# TrashFullnessSensor1_0_0.net
KiCad netlist of a schematic drawn in Altium Designer
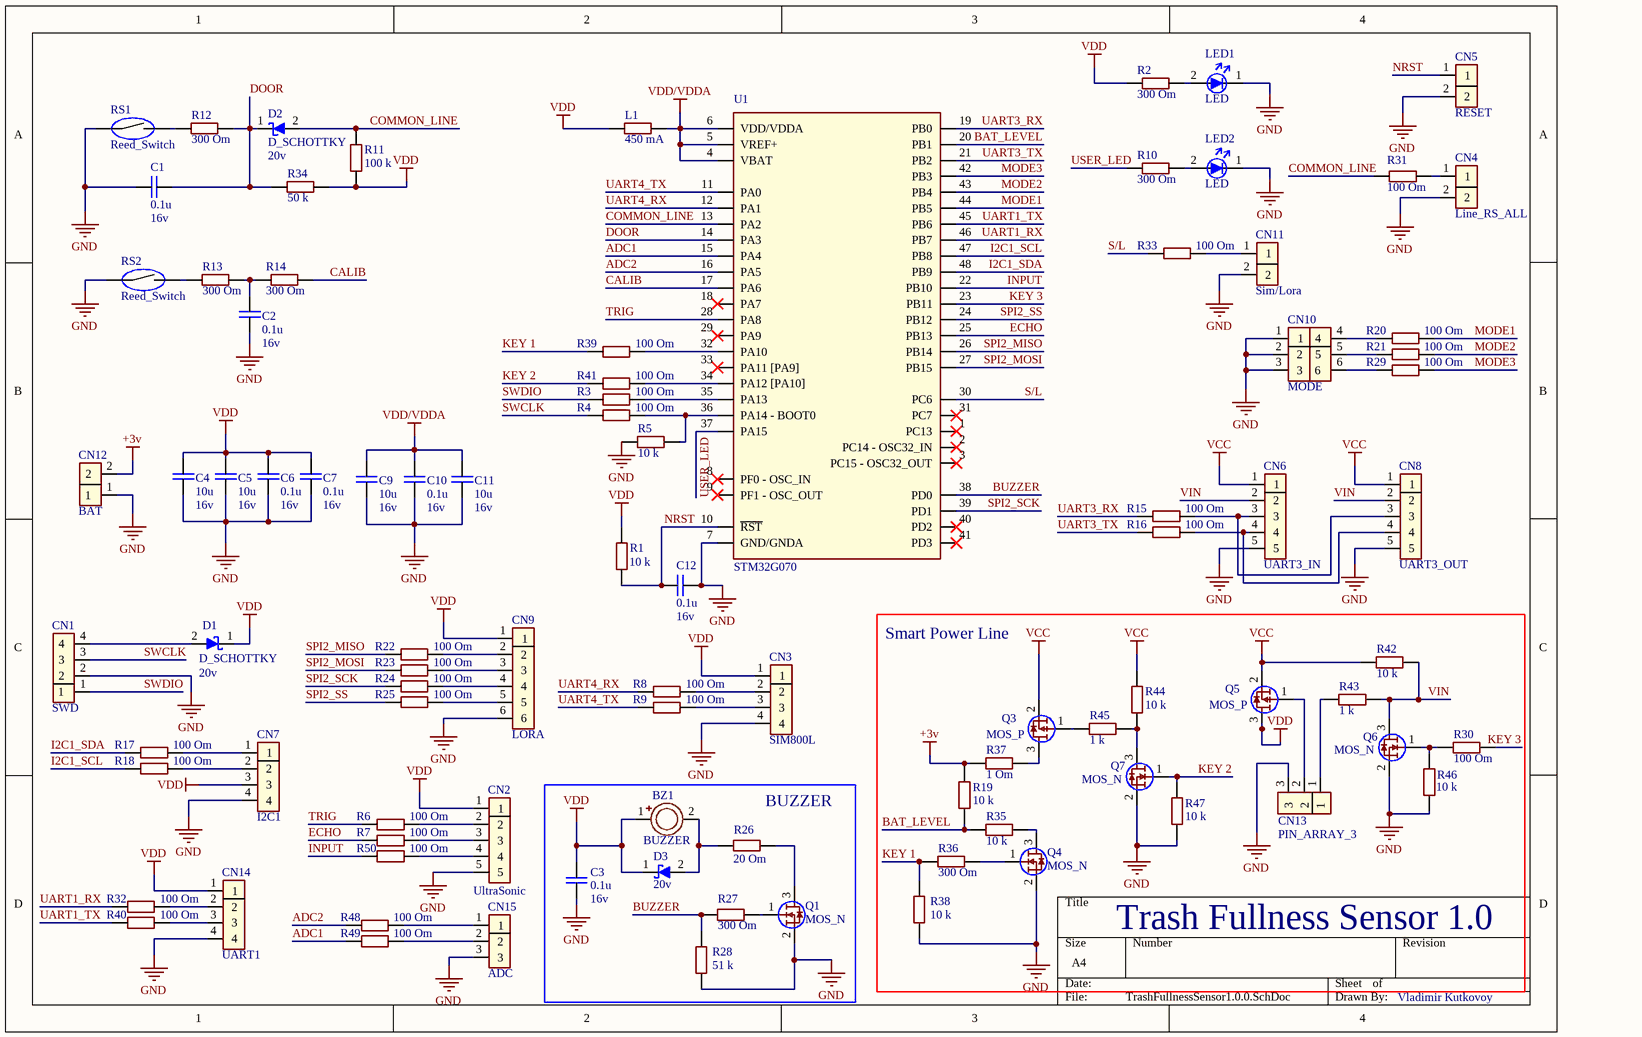
[diagram p0: TrashFullnessSensor1.0.0.SchDoc]

(export (version "E")
  (design (tool "Eeschema 10.0.6"))
  (components
    (comp (ref "BZ1") (value "BUZZER") (footprint "VK_Lib:BUZZER") (libsource (lib "Sound") (part "BUZZER")))
    (comp (ref "C1")
      (value "Capacitor")
      (footprint "VK_Lib:CAPC06003")
      (fields (field (name "СAPACITY") "0.1u") (field (name "VOLTAGE") "16v"))
      (libsource (lib "VK_Lib") (part "Capacitor"))
    )
    (comp (ref "C2")
      (value "Capacitor")
      (footprint "VK_Lib:CAP_0603")
      (fields (field (name "СAPACITY") "0.1u") (field (name "VOLTAGE") "16v"))
      (libsource (lib "PassiveComponents") (part "Capacitor"))
    )
    (comp (ref "C3")
      (value "Capacitor")
      (footprint "VK_Lib:CAP_0603")
      (fields (field (name "СAPACITY") "0.1u") (field (name "VOLTAGE") "16v"))
      (libsource (lib "PassiveComponents") (part "Capacitor"))
    )
    (comp (ref "C4")
      (value "~")
      (footprint "CAPC06003")
      (fields (field (name "СAPACITY") "10u") (field (name "VOLTAGE") "16v"))
      (libsource (lib "PassiveComponents") (part "Capacitor"))
    )
    (comp (ref "C5")
      (value "Capacitor")
      (footprint "VK_Lib:CAPC06003")
      (fields (field (name "СAPACITY") "10u") (field (name "VOLTAGE") "16v"))
      (libsource (lib "VK_Lib") (part "Capacitor"))
    )
    (comp (ref "C6")
      (value "Capacitor")
      (footprint "VK_Lib:CAPC06003")
      (fields (field (name "СAPACITY") "0.1u") (field (name "VOLTAGE") "16v"))
      (libsource (lib "VK_Lib") (part "Capacitor"))
    )
    (comp (ref "C7")
      (value "Capacitor")
      (footprint "VK_Lib:CAPC06003")
      (fields (field (name "СAPACITY") "0.1u") (field (name "VOLTAGE") "16v"))
      (libsource (lib "VK_Lib") (part "Capacitor"))
    )
    (comp (ref "C9")
      (value "Capacitor")
      (footprint "VK_Lib:Cap_0603")
      (fields (field (name "СAPACITY") "10u") (field (name "VOLTAGE") "16v"))
      (libsource (lib "VK_Lib") (part "Capacitor"))
    )
    (comp (ref "C10")
      (value "Capacitor")
      (footprint "VK_Lib:CAP_0603")
      (fields (field (name "СAPACITY") "0.1u") (field (name "VOLTAGE") "16v"))
      (libsource (lib "PassiveComponents") (part "Capacitor"))
    )
    (comp (ref "C11")
      (value "Capacitor")
      (footprint "VK_Lib:Cap_0603")
      (fields (field (name "СAPACITY") "10u") (field (name "VOLTAGE") "16v"))
      (libsource (lib "VK_Lib") (part "Capacitor"))
    )
    (comp (ref "C12")
      (value "Capacitor")
      (footprint "VK_Lib:CAPC06003")
      (fields (field (name "СAPACITY") "0.1u") (field (name "VOLTAGE") "16v"))
      (libsource (lib "VK_Lib") (part "Capacitor"))
    )
    (comp (ref "CN1")
      (value "SWD")
      (footprint "VK_Lib:PIN_2.54_4_array")
      (libsource (lib "Connector") (part "PIN_ARRAY_4"))
    )
    (comp (ref "CN2")
      (value "UltraSonic")
      (footprint "VK_Lib:Pin_2.54_5_Array")
      (libsource (lib "Connector") (part "PIN_ARRAY_5"))
    )
    (comp (ref "CN3")
      (value "SIM800L")
      (footprint "VK_Lib:PIN_2.54_4_array")
      (libsource (lib "") (part "PIN_ARRAY_4_1"))
    )
    (comp (ref "CN4")
      (value "Line_RS_ALL")
      (footprint "VK_Lib:PIN_2.54_2_ARRAY")
      (libsource (lib "") (part "PIN_ARRAY_2_1"))
    )
    (comp (ref "CN5")
      (value "RESET")
      (footprint "VK_Lib:PIN_2.54_2_ARRAY")
      (libsource (lib "") (part "PIN_ARRAY_2_1"))
    )
    (comp (ref "CN6")
      (value "UART3_IN")
      (footprint "VK_Lib:Pin_2.54_5_Array")
      (libsource (lib "Connector") (part "PIN_ARRAY_5"))
    )
    (comp (ref "CN7")
      (value "I2C1")
      (footprint "VK_Lib:PIN_2.54_4_array")
      (libsource (lib "") (part "PIN_ARRAY_4_1"))
    )
    (comp (ref "CN8")
      (value "UART3_OUT")
      (footprint "VK_Lib:Pin_2.54_5_Array")
      (libsource (lib "Connector") (part "PIN_ARRAY_5"))
    )
    (comp (ref "CN9")
      (value "LORA")
      (footprint "VK_Lib:Pin_2.54_6_Array")
      (libsource (lib "Connector") (part "PIN_ARRAY_6"))
    )
    (comp (ref "CN10")
      (value "MODE")
      (footprint "VK_Lib:Pin_2.54_3x2_Array")
      (libsource (lib "Connector") (part "PIN_ARRAY_3x2"))
    )
    (comp (ref "CN11")
      (value "Sim/Lora")
      (footprint "VK_Lib:PIN_2.54_2_ARRAY")
      (libsource (lib "") (part "PIN_ARRAY_2_1"))
    )
    (comp (ref "CN12")
      (value "BAT")
      (footprint "VK_Lib:PIN_2.54_2_ARRAY")
      (libsource (lib "Connector") (part "PIN_ARRAY_2"))
    )
    (comp (ref "CN13")
      (value "PIN_ARRAY_3")
      (footprint "VK_Lib:Pin_2.54_3_Array")
      (libsource (lib "Connector") (part "PIN_ARRAY_3"))
    )
    (comp (ref "CN14")
      (value "UART1")
      (footprint "VK_Lib:PIN_2.54_4_array")
      (libsource (lib "") (part "PIN_ARRAY_4_1"))
    )
    (comp (ref "CN15")
      (value "ADC")
      (footprint "VK_Lib:Pin_2.54_3_Array")
      (libsource (lib "") (part "PIN_ARRAY_3_1"))
    )
    (comp (ref "D1")
      (value "D_SCHOTTKY")
      (footprint "Diod_Shottky")
      (fields (field (name "VOLTAGE") "20v"))
      (libsource (lib "PassiveComponents") (part "Diod_Shottky"))
    )
    (comp (ref "D2")
      (value "D_SCHOTTKY")
      (footprint "Diod_Shottky")
      (fields (field (name "VOLTAGE") "20v"))
      (libsource (lib "PassiveComponents") (part "Diod_Shottky"))
    )
    (comp (ref "D3")
      (value "D_SCHOTTKY")
      (footprint "Diod_Shottky")
      (fields (field (name "VOLTAGE") "20v"))
      (libsource (lib "PassiveComponents") (part "Diod_Shottky"))
    )
    (comp (ref "L1")
      (value "450 mA")
      (footprint "VK_Lib:RES_0603")
      (description "BLM18BB221SN1D")
      (libsource (lib "VK_Lib") (part "Filter"))
    )
    (comp (ref "LED1") (value "LED") (footprint "VK_Lib:Led_0603_Red") (libsource (lib "") (part "LED_1")))
    (comp (ref "LED2")
      (value "LED")
      (footprint "VK_Lib:Led_0603_Red")
      (libsource (lib "PassiveComponents") (part "LED"))
    )
    (comp (ref "Q1") (value "MOS_N") (footprint "SOT23-3") (libsource (lib "Semicon") (part "MOS_N")))
    (comp (ref "Q3") (value "MOS_P") (footprint "SOT23-3") (libsource (lib "Semicon") (part "MOS_P")))
    (comp (ref "Q4") (value "MOS_N") (footprint "SOT23-3") (libsource (lib "Semicon") (part "MOS_N")))
    (comp (ref "Q5") (value "MOS_P") (footprint "SOT23-3") (libsource (lib "Semicon") (part "MOS_P")))
    (comp (ref "Q6") (value "MOS_N") (footprint "SOT23-3") (libsource (lib "Semicon") (part "MOS_N")))
    (comp (ref "Q7") (value "MOS_N") (footprint "SOT23-3") (libsource (lib "Semicon") (part "MOS_N")))
    (comp (ref "R1") (value "10 k") (footprint "VK_Lib:RES_0603") (libsource (lib "") (part "Resistor_1")))
    (comp (ref "R2")
      (value "300 Om")
      (footprint "VK_Lib:RES_0603")
      (libsource (lib "VK_Lib") (part "Resistor"))
    )
    (comp (ref "R3")
      (value "100 Om")
      (footprint "VK_Lib:RES_0603")
      (libsource (lib "VK_Lib") (part "Resistor"))
    )
    (comp (ref "R4")
      (value "100 Om")
      (footprint "VK_Lib:RES_0603")
      (libsource (lib "VK_Lib") (part "Resistor"))
    )
    (comp (ref "R5")
      (value "10 k")
      (footprint "VK_Lib:RES_0603")
      (libsource (lib "VK_Lib") (part "Resistor"))
    )
    (comp (ref "R6")
      (value "100 Om")
      (footprint "VK_Lib:RES_0603")
      (libsource (lib "VK_Lib") (part "Resistor"))
    )
    (comp (ref "R7")
      (value "100 Om")
      (footprint "VK_Lib:RES_0603")
      (libsource (lib "VK_Lib") (part "Resistor"))
    )
    (comp (ref "R8")
      (value "100 Om")
      (footprint "VK_Lib:RES_0603")
      (libsource (lib "VK_Lib") (part "Resistor"))
    )
    (comp (ref "R9")
      (value "100 Om")
      (footprint "VK_Lib:RES_0603")
      (libsource (lib "VK_Lib") (part "Resistor"))
    )
    (comp (ref "R10")
      (value "300 Om")
      (footprint "VK_Lib:RES_0603")
      (libsource (lib "VK_Lib") (part "Resistor"))
    )
    (comp (ref "R11") (value "100 k") (footprint "VK_Lib:RES_0603") (libsource (lib "") (part "Resistor_1")))
    (comp (ref "R12") (value "300 Om") (footprint "VK_Lib:RES_0603") (libsource (lib "") (part "Resistor_2")))
    (comp (ref "R13") (value "300 Om") (footprint "VK_Lib:RES_0603") (libsource (lib "") (part "Resistor_2")))
    (comp (ref "R14")
      (value "300 Om")
      (footprint "VK_Lib:RES_0603")
      (libsource (lib "VK_Lib") (part "Resistor"))
    )
    (comp (ref "R15")
      (value "100 Om")
      (footprint "VK_Lib:RES_0603")
      (libsource (lib "VK_Lib") (part "Resistor"))
    )
    (comp (ref "R16")
      (value "100 Om")
      (footprint "VK_Lib:RES_0603")
      (libsource (lib "VK_Lib") (part "Resistor"))
    )
    (comp (ref "R17")
      (value "100 Om")
      (footprint "VK_Lib:RES_0603")
      (libsource (lib "VK_Lib") (part "Resistor"))
    )
    (comp (ref "R18")
      (value "100 Om")
      (footprint "VK_Lib:RES_0603")
      (libsource (lib "VK_Lib") (part "Resistor"))
    )
    (comp (ref "R19")
      (value "10 k")
      (footprint "VK_Lib:RES_0603")
      (libsource (lib "PassiveComponents") (part "Resistor"))
    )
    (comp (ref "R20")
      (value "100 Om")
      (footprint "VK_Lib:RES_0603")
      (libsource (lib "VK_Lib") (part "Resistor"))
    )
    (comp (ref "R21")
      (value "100 Om")
      (footprint "VK_Lib:RES_0603")
      (libsource (lib "VK_Lib") (part "Resistor"))
    )
    (comp (ref "R22")
      (value "100 Om")
      (footprint "VK_Lib:RES_0603")
      (libsource (lib "VK_Lib") (part "Resistor"))
    )
    (comp (ref "R23")
      (value "100 Om")
      (footprint "VK_Lib:RES_0603")
      (libsource (lib "VK_Lib") (part "Resistor"))
    )
    (comp (ref "R24")
      (value "100 Om")
      (footprint "VK_Lib:RES_0603")
      (libsource (lib "VK_Lib") (part "Resistor"))
    )
    (comp (ref "R25")
      (value "100 Om")
      (footprint "VK_Lib:RES_0603")
      (libsource (lib "VK_Lib") (part "Resistor"))
    )
    (comp (ref "R26") (value "20 Om") (footprint "VK_Lib:RES_0603") (libsource (lib "") (part "Resistor_2")))
    (comp (ref "R27") (value "300 Om") (footprint "VK_Lib:RES_0603") (libsource (lib "") (part "Resistor_2")))
    (comp (ref "R28")
      (value "51 k")
      (footprint "VK_Lib:RES_0603")
      (libsource (lib "PassiveComponents") (part "Resistor"))
    )
    (comp (ref "R29")
      (value "100 Om")
      (footprint "VK_Lib:RES_0603")
      (libsource (lib "VK_Lib") (part "Resistor"))
    )
    (comp (ref "R30") (value "100 Om") (footprint "VK_Lib:RES_0603") (libsource (lib "") (part "Resistor_3")))
    (comp (ref "R31")
      (value "100 Om")
      (footprint "VK_Lib:RES_0603")
      (libsource (lib "VK_Lib") (part "Resistor"))
    )
    (comp (ref "R32")
      (value "100 Om")
      (footprint "VK_Lib:RES_0603")
      (libsource (lib "VK_Lib") (part "Resistor"))
    )
    (comp (ref "R33")
      (value "100 Om")
      (footprint "VK_Lib:RES_0603")
      (libsource (lib "VK_Lib") (part "Resistor"))
    )
    (comp (ref "R34")
      (value "50 k")
      (footprint "VK_Lib:RES_0603")
      (libsource (lib "VK_Lib") (part "Resistor"))
    )
    (comp (ref "R35") (value "10 k") (footprint "VK_Lib:RES_0603") (libsource (lib "") (part "Resistor_3")))
    (comp (ref "R36") (value "300 Om") (footprint "VK_Lib:RES_0603") (libsource (lib "") (part "Resistor_2")))
    (comp (ref "R37") (value "1 Om") (footprint "VK_Lib:Res_0805") (libsource (lib "") (part "Resistor_2")))
    (comp (ref "R38")
      (value "10 k")
      (footprint "VK_Lib:RES_0603")
      (libsource (lib "PassiveComponents") (part "Resistor"))
    )
    (comp (ref "R39")
      (value "100 Om")
      (footprint "VK_Lib:RES_0603")
      (libsource (lib "VK_Lib") (part "Resistor"))
    )
    (comp (ref "R40")
      (value "100 Om")
      (footprint "VK_Lib:RES_0603")
      (libsource (lib "VK_Lib") (part "Resistor"))
    )
    (comp (ref "R41")
      (value "100 Om")
      (footprint "VK_Lib:RES_0603")
      (libsource (lib "VK_Lib") (part "Resistor"))
    )
    (comp (ref "R42") (value "10 k") (footprint "VK_Lib:RES_0603") (libsource (lib "") (part "Resistor_2")))
    (comp (ref "R43") (value "1 k") (footprint "VK_Lib:RES_0603") (libsource (lib "") (part "Resistor_2")))
    (comp (ref "R44") (value "10 k") (footprint "VK_Lib:RES_0603") (libsource (lib "") (part "Resistor_1")))
    (comp (ref "R45") (value "1 k") (footprint "VK_Lib:RES_0603") (libsource (lib "") (part "Resistor_2")))
    (comp (ref "R46")
      (value "10 k")
      (footprint "VK_Lib:RES_0603")
      (libsource (lib "PassiveComponents") (part "Resistor"))
    )
    (comp (ref "R47") (value "10 k") (footprint "VK_Lib:RES_0603") (libsource (lib "") (part "Resistor_1")))
    (comp (ref "R48")
      (value "100 Om")
      (footprint "VK_Lib:RES_0603")
      (libsource (lib "VK_Lib") (part "Resistor"))
    )
    (comp (ref "R49")
      (value "100 Om")
      (footprint "VK_Lib:RES_0603")
      (libsource (lib "VK_Lib") (part "Resistor"))
    )
    (comp (ref "R50")
      (value "100 Om")
      (footprint "VK_Lib:RES_0603")
      (libsource (lib "VK_Lib") (part "Resistor"))
    )
    (comp (ref "RS1")
      (value "Reed_Switch")
      (footprint "VK_Lib:PIN_2.54_2_ARRAY")
      (libsource (lib "Switch") (part "Reed_Switch"))
    )
    (comp (ref "RS2")
      (value "Reed_Switch")
      (footprint "VK_Lib:PIN_2.54_2_ARRAY")
      (libsource (lib "Switch") (part "Reed_Switch"))
    )
    (comp (ref "U1")
      (value "STM32G070")
      (footprint "VK_Lib:LQFP48")
      (libsource (lib "Processors") (part "STM32G070"))
    )
  )
  (nets
    (net (code "1") (name "+3v") (class "Default")
      (node (ref "CN12") (pin "2") (pinfunction "2_2") (pintype "passive"))
      (node (ref "R19") (pin "2") (pinfunction "2_2") (pintype "passive"))
      (node (ref "R37") (pin "1") (pinfunction "1_1") (pintype "passive"))
    )
    (net (code "2") (name "/ADC1") (class "Default")
      (node (ref "R49") (pin "1") (pinfunction "1_1") (pintype "passive"))
      (node (ref "U1") (pin "15") (pinfunction "PA4_15") (pintype "passive"))
    )
    (net (code "3") (name "/ADC2") (class "Default")
      (node (ref "R48") (pin "1") (pinfunction "1_1") (pintype "passive"))
      (node (ref "U1") (pin "16") (pinfunction "PA5_16") (pintype "passive"))
    )
    (net (code "4") (name "/BAT_LEVEL") (class "Default")
      (node (ref "R19") (pin "1") (pinfunction "1_1") (pintype "passive"))
      (node (ref "R35") (pin "2") (pinfunction "2_2") (pintype "passive"))
      (node (ref "U1") (pin "20") (pinfunction "PB1_20") (pintype "passive"))
    )
    (net (code "5") (name "/BUZZER") (class "Default")
      (node (ref "R27") (pin "1") (pinfunction "1_1") (pintype "passive"))
      (node (ref "R28") (pin "2") (pinfunction "2_2") (pintype "passive"))
      (node (ref "U1") (pin "38") (pinfunction "PD0_38") (pintype "passive"))
    )
    (net (code "6") (name "/CALIB") (class "Default")
      (node (ref "R14") (pin "2") (pinfunction "2_2") (pintype "passive"))
      (node (ref "U1") (pin "17") (pinfunction "PA6_17") (pintype "passive"))
    )
    (net (code "7") (name "/COMMON_LINE") (class "Default")
      (node (ref "D2") (pin "2") (pinfunction "2_2") (pintype "passive"))
      (node (ref "R11") (pin "2") (pinfunction "2_2") (pintype "passive"))
      (node (ref "R31") (pin "1") (pinfunction "1_1") (pintype "passive"))
      (node (ref "U1") (pin "13") (pinfunction "PA2_13") (pintype "passive"))
    )
    (net (code "8") (name "/DOOR") (class "Default")
      (node (ref "C1") (pin "1") (pinfunction "1_1") (pintype "passive"))
      (node (ref "D2") (pin "1") (pinfunction "1_1") (pintype "passive"))
      (node (ref "R12") (pin "1") (pinfunction "1_1") (pintype "passive"))
      (node (ref "R34") (pin "1") (pinfunction "1_1") (pintype "passive"))
      (node (ref "U1") (pin "14") (pinfunction "PA3_14") (pintype "passive"))
    )
    (net (code "9") (name "/ECHO") (class "Default")
      (node (ref "R7") (pin "1") (pinfunction "1_1") (pintype "passive"))
      (node (ref "U1") (pin "25") (pinfunction "PB13_25") (pintype "passive"))
    )
    (net (code "10") (name "/I2C1_SCL") (class "Default")
      (node (ref "R18") (pin "1") (pinfunction "1_1") (pintype "passive"))
      (node (ref "U1") (pin "47") (pinfunction "PB8_47") (pintype "passive"))
    )
    (net (code "11") (name "/I2C1_SDA") (class "Default")
      (node (ref "R17") (pin "1") (pinfunction "1_1") (pintype "passive"))
      (node (ref "U1") (pin "48") (pinfunction "PB9_48") (pintype "passive"))
    )
    (net (code "12") (name "/INPUT") (class "Default")
      (node (ref "R50") (pin "1") (pinfunction "1_1") (pintype "passive"))
      (node (ref "U1") (pin "22") (pinfunction "PB10_22") (pintype "passive"))
    )
    (net (code "13") (name "/KEY 1") (class "Default")
      (node (ref "R36") (pin "1") (pinfunction "1_1") (pintype "passive"))
      (node (ref "R38") (pin "2") (pinfunction "2_2") (pintype "passive"))
      (node (ref "R39") (pin "1") (pinfunction "1_1") (pintype "passive"))
    )
    (net (code "14") (name "/KEY 2") (class "Default")
      (node (ref "Q7") (pin "1") (pinfunction "G_1") (pintype "passive"))
      (node (ref "R41") (pin "1") (pinfunction "1_1") (pintype "passive"))
      (node (ref "R47") (pin "1") (pinfunction "1_1") (pintype "passive"))
    )
    (net (code "15") (name "/KEY 3") (class "Default")
      (node (ref "R30") (pin "1") (pinfunction "1_1") (pintype "passive"))
      (node (ref "U1") (pin "23") (pinfunction "PB11_23") (pintype "passive"))
    )
    (net (code "16") (name "/MODE1") (class "Default")
      (node (ref "R20") (pin "2") (pinfunction "2_2") (pintype "passive"))
      (node (ref "U1") (pin "44") (pinfunction "PB5_44") (pintype "passive"))
    )
    (net (code "17") (name "/MODE2") (class "Default")
      (node (ref "R21") (pin "2") (pinfunction "2_2") (pintype "passive"))
      (node (ref "U1") (pin "43") (pinfunction "PB4_43") (pintype "passive"))
    )
    (net (code "18") (name "/MODE3") (class "Default")
      (node (ref "R29") (pin "2") (pinfunction "2_2") (pintype "passive"))
      (node (ref "U1") (pin "42") (pinfunction "PB3_42") (pintype "passive"))
    )
    (net (code "19") (name "/NRST") (class "Default")
      (node (ref "C12") (pin "2") (pinfunction "2_2") (pintype "passive"))
      (node (ref "CN5") (pin "1") (pinfunction "1_1") (pintype "passive"))
      (node (ref "R1") (pin "1") (pinfunction "1_1") (pintype "passive"))
      (node (ref "U1") (pin "10") (pinfunction "~{RST}_10") (pintype "passive"))
    )
    (net (code "20") (name "/SPI2_MISO") (class "Default")
      (node (ref "R22") (pin "1") (pinfunction "1_1") (pintype "passive"))
      (node (ref "U1") (pin "26") (pinfunction "PB14_26") (pintype "passive"))
    )
    (net (code "21") (name "/SPI2_MOSI") (class "Default")
      (node (ref "R23") (pin "1") (pinfunction "1_1") (pintype "passive"))
      (node (ref "U1") (pin "27") (pinfunction "PB15_27") (pintype "passive"))
    )
    (net (code "22") (name "/SPI2_SCK") (class "Default")
      (node (ref "R24") (pin "1") (pinfunction "1_1") (pintype "passive"))
      (node (ref "U1") (pin "39") (pinfunction "PD1_39") (pintype "passive"))
    )
    (net (code "23") (name "/SPI2_SS") (class "Default")
      (node (ref "R25") (pin "1") (pinfunction "1_1") (pintype "passive"))
      (node (ref "U1") (pin "24") (pinfunction "PB12_24") (pintype "passive"))
    )
    (net (code "24") (name "/SWCLK") (class "Default")
      (node (ref "CN1") (pin "3") (pinfunction "3_3") (pintype "passive"))
      (node (ref "R4") (pin "1") (pinfunction "1_1") (pintype "passive"))
    )
    (net (code "25") (name "/SWDIO") (class "Default")
      (node (ref "CN1") (pin "1") (pinfunction "1_1") (pintype "passive"))
      (node (ref "R3") (pin "1") (pinfunction "1_1") (pintype "passive"))
    )
    (net (code "26") (name "/S{slash}L") (class "Default")
      (node (ref "R33") (pin "1") (pinfunction "1_1") (pintype "passive"))
      (node (ref "U1") (pin "30") (pinfunction "PС6_30") (pintype "passive"))
    )
    (net (code "27") (name "/TRIG") (class "Default")
      (node (ref "R6") (pin "1") (pinfunction "1_1") (pintype "passive"))
      (node (ref "U1") (pin "28") (pinfunction "PA8_28") (pintype "passive"))
    )
    (net (code "28") (name "/UART1_RX") (class "Default")
      (node (ref "R32") (pin "1") (pinfunction "1_1") (pintype "passive"))
      (node (ref "U1") (pin "46") (pinfunction "PB7_46") (pintype "passive"))
    )
    (net (code "29") (name "/UART1_TX") (class "Default")
      (node (ref "R40") (pin "1") (pinfunction "1_1") (pintype "passive"))
      (node (ref "U1") (pin "45") (pinfunction "PB6_45") (pintype "passive"))
    )
    (net (code "30") (name "/UART3_RX") (class "Default")
      (node (ref "R15") (pin "1") (pinfunction "1_1") (pintype "passive"))
      (node (ref "U1") (pin "19") (pinfunction "PB0_19") (pintype "passive"))
    )
    (net (code "31") (name "/UART3_TX") (class "Default")
      (node (ref "R16") (pin "1") (pinfunction "1_1") (pintype "passive"))
      (node (ref "U1") (pin "21") (pinfunction "PB2_21") (pintype "passive"))
    )
    (net (code "32") (name "/UART4_RX") (class "Default")
      (node (ref "R8") (pin "1") (pinfunction "1_1") (pintype "passive"))
      (node (ref "U1") (pin "12") (pinfunction "PA1_12") (pintype "passive"))
    )
    (net (code "33") (name "/UART4_TX") (class "Default")
      (node (ref "R9") (pin "1") (pinfunction "1_1") (pintype "passive"))
      (node (ref "U1") (pin "11") (pinfunction "PA0_11") (pintype "passive"))
    )
    (net (code "34") (name "/USER_LED") (class "Default")
      (node (ref "R10") (pin "1") (pinfunction "1_1") (pintype "passive"))
      (node (ref "U1") (pin "37") (pinfunction "PA15_37") (pintype "passive"))
    )
    (net (code "35") (name "/VIN") (class "Default")
      (node (ref "CN6") (pin "2") (pinfunction "2_2") (pintype "passive"))
      (node (ref "CN8") (pin "2") (pinfunction "2_2") (pintype "passive"))
      (node (ref "Q6") (pin "3") (pinfunction "D_3") (pintype "passive"))
      (node (ref "R42") (pin "2") (pinfunction "2_2") (pintype "passive"))
      (node (ref "R43") (pin "2") (pinfunction "2_2") (pintype "passive"))
    )
    (net (code "36") (name "GND") (class "Default")
      (node (ref "C1") (pin "2") (pinfunction "2_2") (pintype "passive"))
      (node (ref "C10") (pin "1") (pinfunction "1_1") (pintype "passive"))
      (node (ref "C11") (pin "1") (pinfunction "1_1") (pintype "passive"))
      (node (ref "C12") (pin "1") (pinfunction "1_1") (pintype "passive"))
      (node (ref "C2") (pin "1") (pinfunction "1_1") (pintype "passive"))
      (node (ref "C3") (pin "1") (pinfunction "1_1") (pintype "passive"))
      (node (ref "C4") (pin "1") (pinfunction "1_1") (pintype "passive"))
      (node (ref "C5") (pin "1") (pinfunction "1_1") (pintype "passive"))
      (node (ref "C6") (pin "1") (pinfunction "1_1") (pintype "passive"))
      (node (ref "C7") (pin "1") (pinfunction "1_1") (pintype "passive"))
      (node (ref "C9") (pin "1") (pinfunction "1_1") (pintype "passive"))
      (node (ref "CN1") (pin "2") (pinfunction "2_2") (pintype "passive"))
      (node (ref "CN10") (pin "1") (pinfunction "1_1") (pintype "passive"))
      (node (ref "CN10") (pin "2") (pinfunction "2_2") (pintype "passive"))
      (node (ref "CN10") (pin "3") (pinfunction "3_3") (pintype "passive"))
      (node (ref "CN11") (pin "2") (pinfunction "2_2") (pintype "passive"))
      (node (ref "CN12") (pin "1") (pinfunction "1_1") (pintype "passive"))
      (node (ref "CN13") (pin "3") (pinfunction "3_3") (pintype "passive"))
      (node (ref "CN14") (pin "4") (pinfunction "4_4") (pintype "passive"))
      (node (ref "CN15") (pin "3") (pinfunction "3_3") (pintype "passive"))
      (node (ref "CN2") (pin "5") (pinfunction "5_5") (pintype "passive"))
      (node (ref "CN3") (pin "4") (pinfunction "4_4") (pintype "passive"))
      (node (ref "CN4") (pin "2") (pinfunction "2_2") (pintype "passive"))
      (node (ref "CN5") (pin "2") (pinfunction "2_2") (pintype "passive"))
      (node (ref "CN6") (pin "5") (pinfunction "5_5") (pintype "passive"))
      (node (ref "CN7") (pin "4") (pinfunction "4_4") (pintype "passive"))
      (node (ref "CN8") (pin "5") (pinfunction "5_5") (pintype "passive"))
      (node (ref "CN9") (pin "6") (pinfunction "6_6") (pintype "passive"))
      (node (ref "LED1") (pin "1") (pinfunction "1_1") (pintype "passive"))
      (node (ref "LED2") (pin "1") (pinfunction "1_1") (pintype "passive"))
      (node (ref "Q1") (pin "2") (pinfunction "S_2") (pintype "passive"))
      (node (ref "Q4") (pin "2") (pinfunction "S_2") (pintype "passive"))
      (node (ref "Q6") (pin "2") (pinfunction "S_2") (pintype "passive"))
      (node (ref "Q7") (pin "2") (pinfunction "S_2") (pintype "passive"))
      (node (ref "R28") (pin "1") (pinfunction "1_1") (pintype "passive"))
      (node (ref "R38") (pin "1") (pinfunction "1_1") (pintype "passive"))
      (node (ref "R46") (pin "1") (pinfunction "1_1") (pintype "passive"))
      (node (ref "R47") (pin "2") (pinfunction "2_2") (pintype "passive"))
      (node (ref "R5") (pin "1") (pinfunction "1_1") (pintype "passive"))
      (node (ref "RS1") (pin "1") (pinfunction "1_1") (pintype "passive"))
      (node (ref "RS2") (pin "1") (pinfunction "1_1") (pintype "passive"))
      (node (ref "U1") (pin "7") (pinfunction "GND/GNDA_7") (pintype "power_in"))
    )
    (net (code "37") (name "Net-(BZ1-Pad2)") (class "Default")
      (node (ref "BZ1") (pin "2") (pinfunction "2_2") (pintype "passive"))
      (node (ref "D3") (pin "2") (pinfunction "2_2") (pintype "passive"))
      (node (ref "R26") (pin "1") (pinfunction "1_1") (pintype "passive"))
    )
    (net (code "38") (name "Net-(C2-Pad2)") (class "Default")
      (node (ref "C2") (pin "2") (pinfunction "2_2") (pintype "passive"))
      (node (ref "R13") (pin "1") (pinfunction "1_1") (pintype "passive"))
      (node (ref "R14") (pin "1") (pinfunction "1_1") (pintype "passive"))
    )
    (net (code "39") (name "Net-(CN1-Pad4)") (class "Default")
      (node (ref "CN1") (pin "4") (pinfunction "4_4") (pintype "passive"))
      (node (ref "D1") (pin "2") (pinfunction "2_2") (pintype "passive"))
    )
    (net (code "40") (name "Net-(CN2-Pad2)") (class "Default")
      (node (ref "CN2") (pin "2") (pinfunction "2_2") (pintype "passive"))
      (node (ref "R6") (pin "2") (pinfunction "2_2") (pintype "passive"))
    )
    (net (code "41") (name "Net-(CN2-Pad3)") (class "Default")
      (node (ref "CN2") (pin "3") (pinfunction "3_3") (pintype "passive"))
      (node (ref "R7") (pin "2") (pinfunction "2_2") (pintype "passive"))
    )
    (net (code "42") (name "Net-(CN2-Pad4)") (class "Default")
      (node (ref "CN2") (pin "4") (pinfunction "4_4") (pintype "passive"))
      (node (ref "R50") (pin "2") (pinfunction "2_2") (pintype "passive"))
    )
    (net (code "43") (name "Net-(CN3-Pad2)") (class "Default")
      (node (ref "CN3") (pin "2") (pinfunction "2_2") (pintype "passive"))
      (node (ref "R8") (pin "2") (pinfunction "2_2") (pintype "passive"))
    )
    (net (code "44") (name "Net-(CN3-Pad3)") (class "Default")
      (node (ref "CN3") (pin "3") (pinfunction "3_3") (pintype "passive"))
      (node (ref "R9") (pin "2") (pinfunction "2_2") (pintype "passive"))
    )
    (net (code "45") (name "Net-(CN4-Pad1)") (class "Default")
      (node (ref "CN4") (pin "1") (pinfunction "1_1") (pintype "passive"))
      (node (ref "R31") (pin "2") (pinfunction "2_2") (pintype "passive"))
    )
    (net (code "46") (name "Net-(CN6-Pad3)") (class "Default")
      (node (ref "CN6") (pin "3") (pinfunction "3_3") (pintype "passive"))
      (node (ref "CN8") (pin "3") (pinfunction "3_3") (pintype "passive"))
      (node (ref "R15") (pin "2") (pinfunction "2_2") (pintype "passive"))
    )
    (net (code "47") (name "Net-(CN6-Pad4)") (class "Default")
      (node (ref "CN6") (pin "4") (pinfunction "4_4") (pintype "passive"))
      (node (ref "CN8") (pin "4") (pinfunction "4_4") (pintype "passive"))
      (node (ref "R16") (pin "2") (pinfunction "2_2") (pintype "passive"))
    )
    (net (code "48") (name "Net-(CN7-Pad1)") (class "Default")
      (node (ref "CN7") (pin "1") (pinfunction "1_1") (pintype "passive"))
      (node (ref "R17") (pin "2") (pinfunction "2_2") (pintype "passive"))
    )
    (net (code "49") (name "Net-(CN7-Pad2)") (class "Default")
      (node (ref "CN7") (pin "2") (pinfunction "2_2") (pintype "passive"))
      (node (ref "R18") (pin "2") (pinfunction "2_2") (pintype "passive"))
    )
    (net (code "50") (name "Net-(CN9-Pad2)") (class "Default")
      (node (ref "CN9") (pin "2") (pinfunction "2_2") (pintype "passive"))
      (node (ref "R22") (pin "2") (pinfunction "2_2") (pintype "passive"))
    )
    (net (code "51") (name "Net-(CN9-Pad3)") (class "Default")
      (node (ref "CN9") (pin "3") (pinfunction "3_3") (pintype "passive"))
      (node (ref "R23") (pin "2") (pinfunction "2_2") (pintype "passive"))
    )
    (net (code "52") (name "Net-(CN9-Pad4)") (class "Default")
      (node (ref "CN9") (pin "4") (pinfunction "4_4") (pintype "passive"))
      (node (ref "R24") (pin "2") (pinfunction "2_2") (pintype "passive"))
    )
    (net (code "53") (name "Net-(CN9-Pad5)") (class "Default")
      (node (ref "CN9") (pin "5") (pinfunction "5_5") (pintype "passive"))
      (node (ref "R25") (pin "2") (pinfunction "2_2") (pintype "passive"))
    )
    (net (code "54") (name "Net-(CN10-Pad4)") (class "Default")
      (node (ref "CN10") (pin "4") (pinfunction "4_4") (pintype "passive"))
      (node (ref "R20") (pin "1") (pinfunction "1_1") (pintype "passive"))
    )
    (net (code "55") (name "Net-(CN10-Pad5)") (class "Default")
      (node (ref "CN10") (pin "5") (pinfunction "5_5") (pintype "passive"))
      (node (ref "R21") (pin "1") (pinfunction "1_1") (pintype "passive"))
    )
    (net (code "56") (name "Net-(CN10-Pad6)") (class "Default")
      (node (ref "CN10") (pin "6") (pinfunction "6_6") (pintype "passive"))
      (node (ref "R29") (pin "1") (pinfunction "1_1") (pintype "passive"))
    )
    (net (code "57") (name "Net-(CN11-Pad1)") (class "Default")
      (node (ref "CN11") (pin "1") (pinfunction "1_1") (pintype "passive"))
      (node (ref "R33") (pin "2") (pinfunction "2_2") (pintype "passive"))
    )
    (net (code "58") (name "Net-(CN13-Pad1)") (class "Default")
      (node (ref "CN13") (pin "1") (pinfunction "1_1") (pintype "passive"))
      (node (ref "R43") (pin "1") (pinfunction "1_1") (pintype "passive"))
    )
    (net (code "59") (name "Net-(CN14-Pad2)") (class "Default")
      (node (ref "CN14") (pin "2") (pinfunction "2_2") (pintype "passive"))
      (node (ref "R32") (pin "2") (pinfunction "2_2") (pintype "passive"))
    )
    (net (code "60") (name "Net-(CN14-Pad3)") (class "Default")
      (node (ref "CN14") (pin "3") (pinfunction "3_3") (pintype "passive"))
      (node (ref "R40") (pin "2") (pinfunction "2_2") (pintype "passive"))
    )
    (net (code "61") (name "Net-(CN15-Pad1)") (class "Default")
      (node (ref "CN15") (pin "1") (pinfunction "1_1") (pintype "passive"))
      (node (ref "R48") (pin "2") (pinfunction "2_2") (pintype "passive"))
    )
    (net (code "62") (name "Net-(CN15-Pad2)") (class "Default")
      (node (ref "CN15") (pin "2") (pinfunction "2_2") (pintype "passive"))
      (node (ref "R49") (pin "2") (pinfunction "2_2") (pintype "passive"))
    )
    (net (code "63") (name "Net-(LED1-Pad2)") (class "Default")
      (node (ref "LED1") (pin "2") (pinfunction "2_2") (pintype "passive"))
      (node (ref "R2") (pin "2") (pinfunction "2_2") (pintype "passive"))
    )
    (net (code "64") (name "Net-(LED2-Pad2)") (class "Default")
      (node (ref "LED2") (pin "2") (pinfunction "2_2") (pintype "passive"))
      (node (ref "R10") (pin "2") (pinfunction "2_2") (pintype "passive"))
    )
    (net (code "65") (name "Net-(Q1-D)") (class "Default")
      (node (ref "Q1") (pin "3") (pinfunction "D_3") (pintype "passive"))
      (node (ref "R26") (pin "2") (pinfunction "2_2") (pintype "passive"))
    )
    (net (code "66") (name "Net-(Q1-G)") (class "Default")
      (node (ref "Q1") (pin "1") (pinfunction "G_1") (pintype "passive"))
      (node (ref "R27") (pin "2") (pinfunction "2_2") (pintype "passive"))
    )
    (net (code "67") (name "Net-(Q3-D)") (class "Default")
      (node (ref "Q3") (pin "3") (pinfunction "D_3") (pintype "passive"))
      (node (ref "R37") (pin "2") (pinfunction "2_2") (pintype "passive"))
    )
    (net (code "68") (name "Net-(Q3-G)") (class "Default")
      (node (ref "Q3") (pin "1") (pinfunction "G_1") (pintype "passive"))
      (node (ref "R45") (pin "1") (pinfunction "1_1") (pintype "passive"))
    )
    (net (code "69") (name "Net-(Q4-D)") (class "Default")
      (node (ref "Q4") (pin "3") (pinfunction "D_3") (pintype "passive"))
      (node (ref "R35") (pin "1") (pinfunction "1_1") (pintype "passive"))
    )
    (net (code "70") (name "Net-(Q4-G)") (class "Default")
      (node (ref "Q4") (pin "1") (pinfunction "G_1") (pintype "passive"))
      (node (ref "R36") (pin "2") (pinfunction "2_2") (pintype "passive"))
    )
    (net (code "71") (name "Net-(Q5-G)") (class "Default")
      (node (ref "CN13") (pin "2") (pinfunction "2_2") (pintype "passive"))
      (node (ref "Q5") (pin "1") (pinfunction "G_1") (pintype "passive"))
    )
    (net (code "72") (name "Net-(Q6-G)") (class "Default")
      (node (ref "Q6") (pin "1") (pinfunction "G_1") (pintype "passive"))
      (node (ref "R30") (pin "2") (pinfunction "2_2") (pintype "passive"))
      (node (ref "R46") (pin "2") (pinfunction "2_2") (pintype "passive"))
    )
    (net (code "73") (name "Net-(Q7-D)") (class "Default")
      (node (ref "Q7") (pin "3") (pinfunction "D_3") (pintype "passive"))
      (node (ref "R44") (pin "2") (pinfunction "2_2") (pintype "passive"))
      (node (ref "R45") (pin "2") (pinfunction "2_2") (pintype "passive"))
    )
    (net (code "74") (name "Net-(R12-Pad2)") (class "Default")
      (node (ref "R12") (pin "2") (pinfunction "2_2") (pintype "passive"))
      (node (ref "RS1") (pin "2") (pinfunction "2_2") (pintype "passive"))
    )
    (net (code "75") (name "Net-(R13-Pad2)") (class "Default")
      (node (ref "R13") (pin "2") (pinfunction "2_2") (pintype "passive"))
      (node (ref "RS2") (pin "2") (pinfunction "2_2") (pintype "passive"))
    )
    (net (code "76") (name "Net-(U1-PA10)") (class "Default")
      (node (ref "R39") (pin "2") (pinfunction "2_2") (pintype "passive"))
      (node (ref "U1") (pin "32") (pinfunction "PA10_32") (pintype "passive"))
    )
    (net (code "77") (name "Net-(U1-PA12_[PA10])") (class "Default")
      (node (ref "R41") (pin "2") (pinfunction "2_2") (pintype "passive"))
      (node (ref "U1") (pin "34") (pinfunction "PA12_[PA10]_34") (pintype "passive"))
    )
    (net (code "78") (name "Net-(U1-PA13)") (class "Default")
      (node (ref "R3") (pin "2") (pinfunction "2_2") (pintype "passive"))
      (node (ref "U1") (pin "35") (pinfunction "PA13_35") (pintype "passive"))
    )
    (net (code "79") (name "Net-(U1-PA14_-_BOOT0)") (class "Default")
      (node (ref "R4") (pin "2") (pinfunction "2_2") (pintype "passive"))
      (node (ref "R5") (pin "2") (pinfunction "2_2") (pintype "passive"))
      (node (ref "U1") (pin "36") (pinfunction "PA14_-_BOOT0_36") (pintype "passive"))
    )
    (net (code "80") (name "VCC") (class "Default")
      (node (ref "CN6") (pin "1") (pinfunction "1_1") (pintype "passive"))
      (node (ref "CN8") (pin "1") (pinfunction "1_1") (pintype "passive"))
      (node (ref "Q3") (pin "2") (pinfunction "S_2") (pintype "passive"))
      (node (ref "Q5") (pin "2") (pinfunction "S_2") (pintype "passive"))
      (node (ref "R42") (pin "1") (pinfunction "1_1") (pintype "passive"))
      (node (ref "R44") (pin "1") (pinfunction "1_1") (pintype "passive"))
    )
    (net (code "81") (name "VDD") (class "Default")
      (node (ref "BZ1") (pin "1") (pinfunction "1_1") (pintype "passive"))
      (node (ref "C3") (pin "2") (pinfunction "2_2") (pintype "passive"))
      (node (ref "C4") (pin "2") (pinfunction "2_2") (pintype "passive"))
      (node (ref "C5") (pin "2") (pinfunction "2_2") (pintype "passive"))
      (node (ref "C6") (pin "2") (pinfunction "2_2") (pintype "passive"))
      (node (ref "C7") (pin "2") (pinfunction "2_2") (pintype "passive"))
      (node (ref "CN14") (pin "1") (pinfunction "1_1") (pintype "passive"))
      (node (ref "CN2") (pin "1") (pinfunction "1_1") (pintype "passive"))
      (node (ref "CN3") (pin "1") (pinfunction "1_1") (pintype "passive"))
      (node (ref "CN7") (pin "3") (pinfunction "3_3") (pintype "passive"))
      (node (ref "CN9") (pin "1") (pinfunction "1_1") (pintype "passive"))
      (node (ref "D1") (pin "1") (pinfunction "1_1") (pintype "passive"))
      (node (ref "D3") (pin "1") (pinfunction "1_1") (pintype "passive"))
      (node (ref "L1") (pin "1") (pinfunction "1_1") (pintype "passive"))
      (node (ref "Q5") (pin "3") (pinfunction "D_3") (pintype "passive"))
      (node (ref "R1") (pin "2") (pinfunction "2_2") (pintype "passive"))
      (node (ref "R11") (pin "1") (pinfunction "1_1") (pintype "passive"))
      (node (ref "R2") (pin "1") (pinfunction "1_1") (pintype "passive"))
      (node (ref "R34") (pin "2") (pinfunction "2_2") (pintype "passive"))
    )
    (net (code "82") (name "VDD{slash}VDDA") (class "Default")
      (node (ref "C10") (pin "2") (pinfunction "2_2") (pintype "passive"))
      (node (ref "C11") (pin "2") (pinfunction "2_2") (pintype "passive"))
      (node (ref "C9") (pin "2") (pinfunction "2_2") (pintype "passive"))
      (node (ref "L1") (pin "2") (pinfunction "2_2") (pintype "passive"))
      (node (ref "U1") (pin "4") (pinfunction "VBAT_4") (pintype "power_in"))
      (node (ref "U1") (pin "5") (pinfunction "VREF+_5") (pintype "power_in"))
      (node (ref "U1") (pin "6") (pinfunction "VDD/VDDA_6") (pintype "power_in"))
    )
    (net (code "83") (name "unconnected-(U1-PA7-Pad18)") (class "Default")
      (node (ref "U1") (pin "18") (pinfunction "PA7_18") (pintype "passive+no_connect"))
    )
    (net (code "84") (name "unconnected-(U1-PA9-Pad29)") (class "Default")
      (node (ref "U1") (pin "29") (pinfunction "PA9_29") (pintype "passive+no_connect"))
    )
    (net (code "85") (name "unconnected-(U1-PA11_[PA9]-Pad33)") (class "Default")
      (node (ref "U1") (pin "33") (pinfunction "PA11_[PA9]_33") (pintype "passive+no_connect"))
    )
    (net (code "86") (name "unconnected-(U1-PC14_-_OSC32_IN-Pad2)") (class "Default")
      (node (ref "U1") (pin "2") (pinfunction "PC14_-_OSC32_IN_2") (pintype "passive+no_connect"))
    )
    (net (code "87") (name "unconnected-(U1-PC15_-_OSC32_OUT-Pad3)") (class "Default")
      (node (ref "U1") (pin "3") (pinfunction "PC15_-_OSC32_OUT_3") (pintype "passive+no_connect"))
    )
    (net (code "88") (name "unconnected-(U1-PD2-Pad40)") (class "Default")
      (node (ref "U1") (pin "40") (pinfunction "PD2_40") (pintype "passive+no_connect"))
    )
    (net (code "89") (name "unconnected-(U1-PD3-Pad41)") (class "Default")
      (node (ref "U1") (pin "41") (pinfunction "PD3_41") (pintype "passive+no_connect"))
    )
    (net (code "90") (name "unconnected-(U1-PF0_-_OSC_IN-Pad8)") (class "Default")
      (node (ref "U1") (pin "8") (pinfunction "PF0_-_OSC_IN_8") (pintype "passive+no_connect"))
    )
    (net (code "91") (name "unconnected-(U1-PF1_-_OSC_OUT-Pad9)") (class "Default")
      (node (ref "U1") (pin "9") (pinfunction "PF1_-_OSC_OUT_9") (pintype "passive+no_connect"))
    )
    (net (code "92") (name "unconnected-(U1-PС7-Pad31)") (class "Default")
      (node (ref "U1") (pin "31") (pinfunction "PС7_31") (pintype "passive+no_connect"))
    )
    (net (code "93") (name "unconnected-(U1-PС13-Pad1)") (class "Default")
      (node (ref "U1") (pin "1") (pinfunction "PС13_1") (pintype "passive+no_connect"))
    )
  )
)
